# Dimmer_1_3.net
KiCad netlist of a schematic drawn in EAGLE
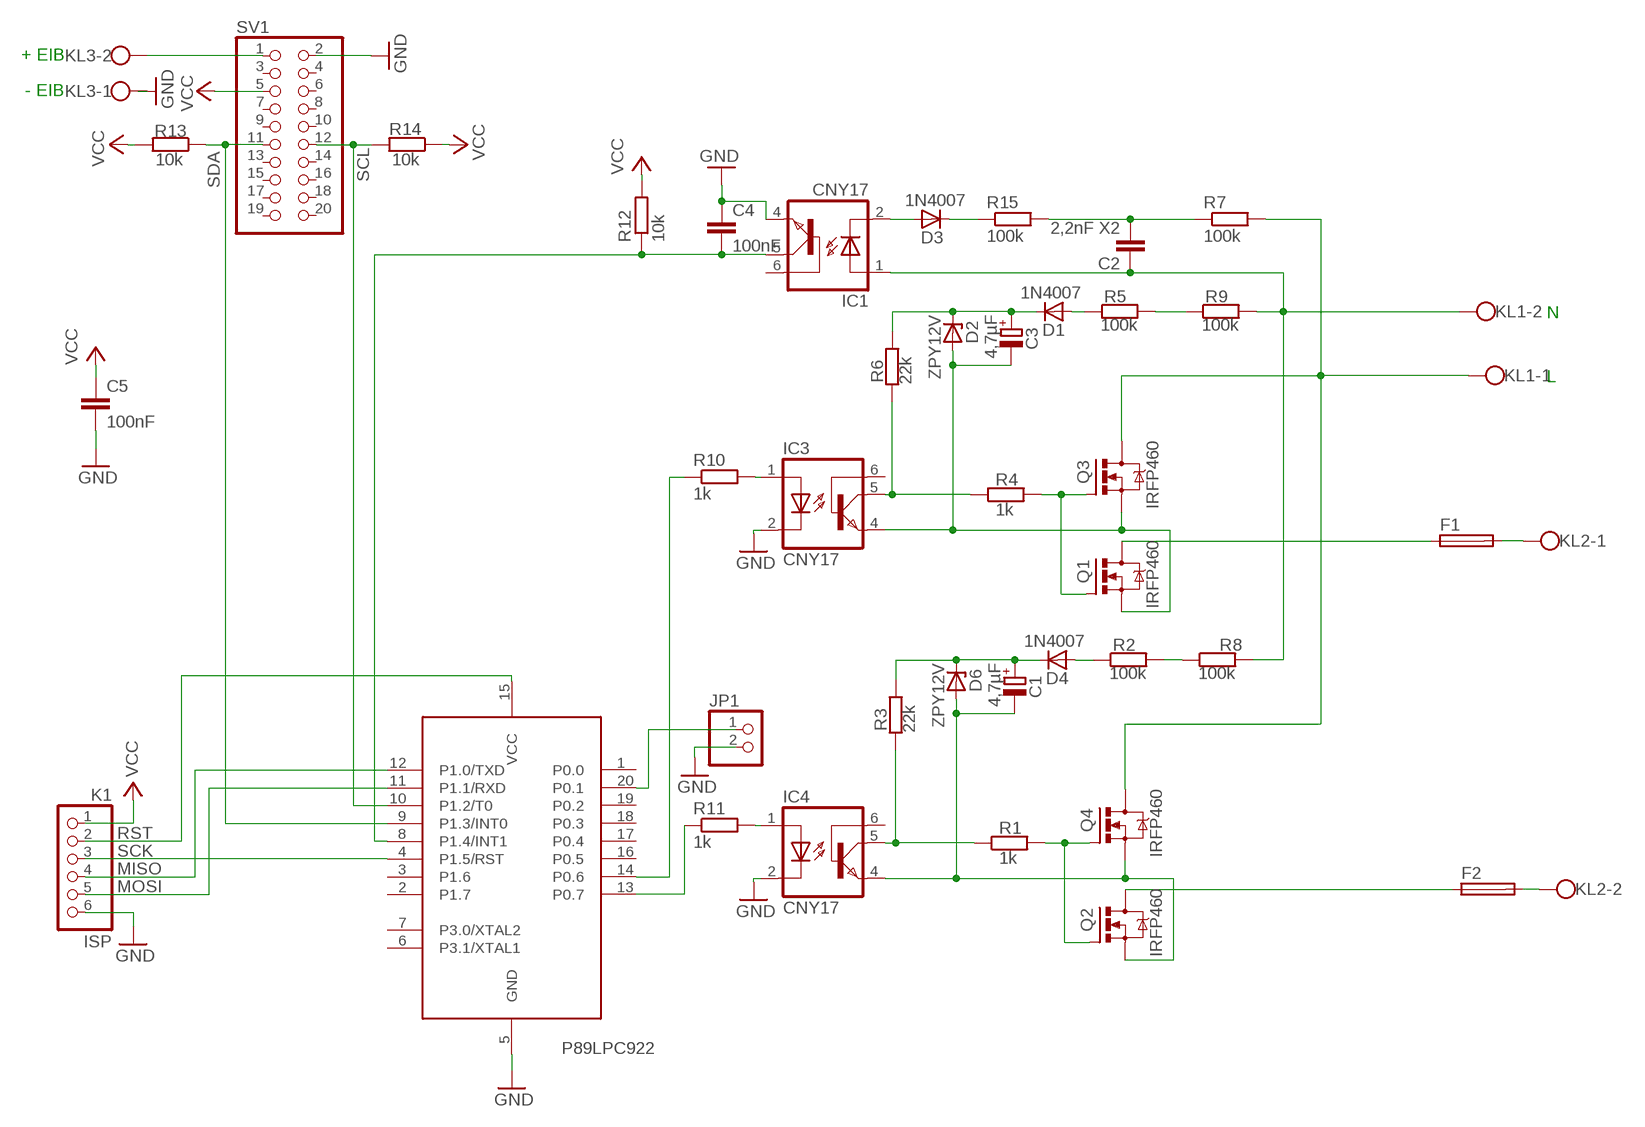
[diagram p0: schematic, sheet 1]

(export (version "E")
  (design (tool "Eeschema 10.0.6"))
  (components
    (comp (ref "C1")
      (value "4,7µF")
      (footprint "eagle-import:E2-4")
      (libsource (lib "eagle-import") (part "CPOL-EUE2-4"))
    )
    (comp (ref "C2")
      (value "2,2nF X2")
      (footprint "eagle-import:C075-063X106")
      (libsource (lib "eagle-import") (part "C-EU075-063X106"))
    )
    (comp (ref "C3")
      (value "4,7µF")
      (footprint "eagle-import:E2-4")
      (libsource (lib "eagle-import") (part "CPOL-EUE2-4"))
    )
    (comp (ref "C4")
      (value "100nF")
      (footprint "eagle-import:C050-024X044")
      (libsource (lib "eagle-import") (part "C-EU050-024X044"))
    )
    (comp (ref "C5")
      (value "100nF")
      (footprint "eagle-import:C025-024X044")
      (libsource (lib "eagle-import") (part "C-EU025-024X044"))
    )
    (comp (ref "D1")
      (value "1N4007")
      (footprint "eagle-import:DO35-10")
      (libsource (lib "eagle-import") (part "1N4148"))
    )
    (comp (ref "D2")
      (value "ZPY12V")
      (footprint "eagle-import:DO41Z10")
      (libsource (lib "eagle-import") (part "ZPY"))
    )
    (comp (ref "D3")
      (value "1N4007")
      (footprint "eagle-import:DO35-10")
      (libsource (lib "eagle-import") (part "1N4148"))
    )
    (comp (ref "D4")
      (value "1N4007")
      (footprint "eagle-import:DO35-10")
      (libsource (lib "eagle-import") (part "1N4148"))
    )
    (comp (ref "D6")
      (value "ZPY12V")
      (footprint "eagle-import:DO41Z10")
      (libsource (lib "eagle-import") (part "ZPY"))
    )
    (comp (ref "F1")
      (value "SH22,5")
      (footprint "eagle-import:SH22,5")
      (libsource (lib "eagle-import") (part "SH22,5"))
    )
    (comp (ref "F2")
      (value "SH22,5")
      (footprint "eagle-import:SH22,5")
      (libsource (lib "eagle-import") (part "SH22,5"))
    )
    (comp (ref "IC1")
      (value "CNY17")
      (footprint "eagle-import:DIL06")
      (libsource (lib "eagle-import") (part "CNY17"))
    )
    (comp (ref "IC2")
      (value "89LPC922")
      (footprint "eagle-import:DIL20")
      (libsource (lib "eagle-import") (part "89LPC922"))
    )
    (comp (ref "IC3")
      (value "CNY17")
      (footprint "eagle-import:DIL06")
      (libsource (lib "eagle-import") (part "CNY17"))
    )
    (comp (ref "IC4")
      (value "CNY17")
      (footprint "eagle-import:DIL06")
      (libsource (lib "eagle-import") (part "CNY17"))
    )
    (comp (ref "JP1")
      (value "PINHD-1X2")
      (footprint "eagle-import:1X02")
      (libsource (lib "eagle-import") (part "PINHD-1X2"))
    )
    (comp (ref "K1")
      (value "ISP")
      (footprint "eagle-import:1X06")
      (libsource (lib "eagle-import") (part "PINHD-1X6"))
    )
    (comp (ref "KL1")
      (value "W237-102")
      (footprint "eagle-import:W237-102")
      (libsource (lib "eagle-import") (part "W237-102"))
    )
    (comp (ref "KL2")
      (value "W237-102")
      (footprint "eagle-import:W237-102")
      (libsource (lib "eagle-import") (part "W237-102"))
    )
    (comp (ref "KL3")
      (value "W237-102")
      (footprint "eagle-import:W237-102")
      (libsource (lib "eagle-import") (part "W237-102"))
    )
    (comp (ref "Q1")
      (value "IRFP460")
      (footprint "eagle-import:TO247BV")
      (libsource (lib "eagle-import") (part "IRFPC40"))
    )
    (comp (ref "Q2")
      (value "IRFP460")
      (footprint "eagle-import:TO247BV")
      (libsource (lib "eagle-import") (part "IRFPC40"))
    )
    (comp (ref "Q3")
      (value "IRFP460")
      (footprint "eagle-import:TO247BV")
      (libsource (lib "eagle-import") (part "IRFPC40"))
    )
    (comp (ref "Q4")
      (value "IRFP460")
      (footprint "eagle-import:TO247BV")
      (libsource (lib "eagle-import") (part "IRFPC40"))
    )
    (comp (ref "R1")
      (value "1k")
      (footprint "eagle-import:0204_7")
      (libsource (lib "eagle-import") (part "R-EU_0204/7"))
    )
    (comp (ref "R2")
      (value "100k")
      (footprint "eagle-import:0204_7")
      (libsource (lib "eagle-import") (part "R-EU_0204/7"))
    )
    (comp (ref "R3")
      (value "22k")
      (footprint "eagle-import:0204_7")
      (libsource (lib "eagle-import") (part "R-EU_0204/7"))
    )
    (comp (ref "R4")
      (value "1k")
      (footprint "eagle-import:0204_7")
      (libsource (lib "eagle-import") (part "R-EU_0204/7"))
    )
    (comp (ref "R5")
      (value "100k")
      (footprint "eagle-import:0204_7")
      (libsource (lib "eagle-import") (part "R-EU_0204/7"))
    )
    (comp (ref "R6")
      (value "22k")
      (footprint "eagle-import:0204_7")
      (libsource (lib "eagle-import") (part "R-EU_0204/7"))
    )
    (comp (ref "R7")
      (value "100k")
      (footprint "eagle-import:0204_7")
      (libsource (lib "eagle-import") (part "R-EU_0204/7"))
    )
    (comp (ref "R8")
      (value "100k")
      (footprint "eagle-import:0204_7")
      (libsource (lib "eagle-import") (part "R-EU_0204/7"))
    )
    (comp (ref "R9")
      (value "100k")
      (footprint "eagle-import:0204_7")
      (libsource (lib "eagle-import") (part "R-EU_0204/7"))
    )
    (comp (ref "R10")
      (value "1k")
      (footprint "eagle-import:0204_7")
      (libsource (lib "eagle-import") (part "R-EU_0204/7"))
    )
    (comp (ref "R11")
      (value "1k")
      (footprint "eagle-import:0204_7")
      (libsource (lib "eagle-import") (part "R-EU_0204/7"))
    )
    (comp (ref "R12")
      (value "10k")
      (footprint "eagle-import:0204_7")
      (libsource (lib "eagle-import") (part "R-EU_0204/7"))
    )
    (comp (ref "R13")
      (value "10k")
      (footprint "eagle-import:0204_7")
      (libsource (lib "eagle-import") (part "R-EU_0204/7"))
    )
    (comp (ref "R14")
      (value "10k")
      (footprint "eagle-import:0204_7")
      (libsource (lib "eagle-import") (part "R-EU_0204/7"))
    )
    (comp (ref "R15")
      (value "100k")
      (footprint "eagle-import:0204_7")
      (libsource (lib "eagle-import") (part "R-EU_0204/7"))
    )
    (comp (ref "SV1")
      (value "PINHD-2X10")
      (footprint "eagle-import:2X10")
      (libsource (lib "eagle-import") (part "PINHD-2X10"))
    )
  )
  (nets
    (net (code "1") (name "/MISO") (class "Default")
      (node (ref "IC2") (pin "12") (pinfunction "P1.0/TXD_12") (pintype "bidirectional"))
      (node (ref "K1") (pin "4") (pinfunction "4_4") (pintype "passive"))
    )
    (net (code "2") (name "/MOSI") (class "Default")
      (node (ref "IC2") (pin "11") (pinfunction "P1.1/RXD_11") (pintype "bidirectional"))
      (node (ref "K1") (pin "5") (pinfunction "5_5") (pintype "passive"))
    )
    (net (code "3") (name "/RST") (class "Default")
      (node (ref "IC2") (pin "15") (pinfunction "VCC_15") (pintype "bidirectional"))
      (node (ref "K1") (pin "2") (pinfunction "2_2") (pintype "passive"))
    )
    (net (code "4") (name "/SCK") (class "Default")
      (node (ref "IC2") (pin "4") (pinfunction "P1.5/RST_4") (pintype "bidirectional"))
      (node (ref "K1") (pin "3") (pinfunction "3_3") (pintype "passive"))
    )
    (net (code "5") (name "/SCL") (class "Default")
      (node (ref "IC2") (pin "10") (pinfunction "P1.2/T0_10") (pintype "bidirectional"))
      (node (ref "R14") (pin "2") (pinfunction "2_2") (pintype "passive"))
      (node (ref "SV1") (pin "12") (pinfunction "12_12") (pintype "passive"))
    )
    (net (code "6") (name "/SDA") (class "Default")
      (node (ref "IC2") (pin "9") (pinfunction "P1.3/INT0_9") (pintype "bidirectional"))
      (node (ref "R13") (pin "1") (pinfunction "1_1") (pintype "passive"))
      (node (ref "SV1") (pin "11") (pinfunction "11_11") (pintype "passive"))
    )
    (net (code "7") (name "GND") (class "Default")
      (node (ref "C4") (pin "1") (pinfunction "1_1") (pintype "passive"))
      (node (ref "C5") (pin "2") (pinfunction "2_2") (pintype "passive"))
      (node (ref "IC1") (pin "4") (pinfunction "EMI_4") (pintype "passive"))
      (node (ref "IC2") (pin "5") (pinfunction "GND_5") (pintype "bidirectional"))
      (node (ref "IC3") (pin "2") (pinfunction "C_2") (pintype "passive"))
      (node (ref "IC4") (pin "2") (pinfunction "C_2") (pintype "passive"))
      (node (ref "JP1") (pin "2") (pinfunction "2_2") (pintype "passive"))
      (node (ref "K1") (pin "6") (pinfunction "6_6") (pintype "passive"))
      (node (ref "KL3") (pin "1") (pinfunction "KL_1") (pintype "passive"))
      (node (ref "SV1") (pin "2") (pinfunction "2_2") (pintype "passive"))
    )
    (net (code "8") (name "Net-(C1-Pad+)") (class "Default")
      (node (ref "C1") (pin "+") (pinfunction "+_+") (pintype "passive"))
      (node (ref "D4") (pin "C") (pinfunction "C_C") (pintype "passive"))
      (node (ref "D6") (pin "C") (pinfunction "C_C") (pintype "passive"))
      (node (ref "R3") (pin "2") (pinfunction "2_2") (pintype "passive"))
    )
    (net (code "9") (name "Net-(C2-Pad2)") (class "Default")
      (node (ref "C2") (pin "2") (pinfunction "2_2") (pintype "passive"))
      (node (ref "R15") (pin "2") (pinfunction "2_2") (pintype "passive"))
      (node (ref "R7") (pin "1") (pinfunction "1_1") (pintype "passive"))
    )
    (net (code "10") (name "Net-(C3-Pad+)") (class "Default")
      (node (ref "C3") (pin "+") (pinfunction "+_+") (pintype "passive"))
      (node (ref "D1") (pin "C") (pinfunction "C_C") (pintype "passive"))
      (node (ref "D2") (pin "C") (pinfunction "C_C") (pintype "passive"))
      (node (ref "R6") (pin "2") (pinfunction "2_2") (pintype "passive"))
    )
    (net (code "11") (name "Net-(D1-PadA)") (class "Default")
      (node (ref "D1") (pin "A") (pinfunction "A_A") (pintype "passive"))
      (node (ref "R5") (pin "1") (pinfunction "1_1") (pintype "passive"))
    )
    (net (code "12") (name "Net-(D3-PadC)") (class "Default")
      (node (ref "D3") (pin "C") (pinfunction "C_C") (pintype "passive"))
      (node (ref "R15") (pin "1") (pinfunction "1_1") (pintype "passive"))
    )
    (net (code "13") (name "Net-(D4-PadA)") (class "Default")
      (node (ref "D4") (pin "A") (pinfunction "A_A") (pintype "passive"))
      (node (ref "R2") (pin "1") (pinfunction "1_1") (pintype "passive"))
    )
    (net (code "14") (name "Net-(F1-Pad1)") (class "Default")
      (node (ref "F1") (pin "1") (pinfunction "1_1") (pintype "passive"))
      (node (ref "Q1") (pin "D") (pinfunction "D_D") (pintype "passive"))
    )
    (net (code "15") (name "Net-(F2-Pad1)") (class "Default")
      (node (ref "F2") (pin "1") (pinfunction "1_1") (pintype "passive"))
      (node (ref "Q2") (pin "D") (pinfunction "D_D") (pintype "passive"))
    )
    (net (code "16") (name "Net-(IC1-A)") (class "Default")
      (node (ref "C2") (pin "1") (pinfunction "1_1") (pintype "passive"))
      (node (ref "IC1") (pin "1") (pinfunction "A_1") (pintype "passive"))
      (node (ref "KL1") (pin "2") (pinfunction "KL_2") (pintype "passive"))
      (node (ref "R8") (pin "2") (pinfunction "2_2") (pintype "passive"))
      (node (ref "R9") (pin "2") (pinfunction "2_2") (pintype "passive"))
    )
    (net (code "17") (name "Net-(IC1-C)") (class "Default")
      (node (ref "D3") (pin "A") (pinfunction "A_A") (pintype "passive"))
      (node (ref "IC1") (pin "2") (pinfunction "C_2") (pintype "passive"))
    )
    (net (code "18") (name "Net-(IC1-COL)") (class "Default")
      (node (ref "C4") (pin "2") (pinfunction "2_2") (pintype "passive"))
      (node (ref "IC1") (pin "5") (pinfunction "COL_5") (pintype "passive"))
      (node (ref "IC2") (pin "8") (pinfunction "P1.4/INT1_8") (pintype "bidirectional"))
      (node (ref "R12") (pin "1") (pinfunction "1_1") (pintype "passive"))
    )
    (net (code "19") (name "Net-(IC2-P0.1)") (class "Default")
      (node (ref "IC2") (pin "20") (pinfunction "P0.1_20") (pintype "bidirectional"))
      (node (ref "JP1") (pin "1") (pinfunction "1_1") (pintype "passive"))
    )
    (net (code "20") (name "Net-(IC2-P0.6)") (class "Default")
      (node (ref "IC2") (pin "14") (pinfunction "P0.6_14") (pintype "bidirectional"))
      (node (ref "R10") (pin "1") (pinfunction "1_1") (pintype "passive"))
    )
    (net (code "21") (name "Net-(IC2-P0.7)") (class "Default")
      (node (ref "IC2") (pin "13") (pinfunction "P0.7_13") (pintype "bidirectional"))
      (node (ref "R11") (pin "1") (pinfunction "1_1") (pintype "passive"))
    )
    (net (code "22") (name "Net-(IC3-A)") (class "Default")
      (node (ref "IC3") (pin "1") (pinfunction "A_1") (pintype "passive"))
      (node (ref "R10") (pin "2") (pinfunction "2_2") (pintype "passive"))
    )
    (net (code "23") (name "Net-(IC3-COL)") (class "Default")
      (node (ref "IC3") (pin "5") (pinfunction "COL_5") (pintype "passive"))
      (node (ref "R4") (pin "1") (pinfunction "1_1") (pintype "passive"))
      (node (ref "R6") (pin "1") (pinfunction "1_1") (pintype "passive"))
    )
    (net (code "24") (name "Net-(IC3-EMI)") (class "Default")
      (node (ref "C3") (pin "-") (pinfunction "-_-") (pintype "passive"))
      (node (ref "D2") (pin "A") (pinfunction "A_A") (pintype "passive"))
      (node (ref "IC3") (pin "4") (pinfunction "EMI_4") (pintype "passive"))
      (node (ref "Q1") (pin "S") (pinfunction "S_S") (pintype "passive"))
      (node (ref "Q3") (pin "S") (pinfunction "S_S") (pintype "passive"))
    )
    (net (code "25") (name "Net-(IC4-A)") (class "Default")
      (node (ref "IC4") (pin "1") (pinfunction "A_1") (pintype "passive"))
      (node (ref "R11") (pin "2") (pinfunction "2_2") (pintype "passive"))
    )
    (net (code "26") (name "Net-(IC4-COL)") (class "Default")
      (node (ref "IC4") (pin "5") (pinfunction "COL_5") (pintype "passive"))
      (node (ref "R1") (pin "1") (pinfunction "1_1") (pintype "passive"))
      (node (ref "R3") (pin "1") (pinfunction "1_1") (pintype "passive"))
    )
    (net (code "27") (name "Net-(IC4-EMI)") (class "Default")
      (node (ref "C1") (pin "-") (pinfunction "-_-") (pintype "passive"))
      (node (ref "D6") (pin "A") (pinfunction "A_A") (pintype "passive"))
      (node (ref "IC4") (pin "4") (pinfunction "EMI_4") (pintype "passive"))
      (node (ref "Q2") (pin "S") (pinfunction "S_S") (pintype "passive"))
      (node (ref "Q4") (pin "S") (pinfunction "S_S") (pintype "passive"))
    )
    (net (code "28") (name "Net-(KL1A-KL)") (class "Default")
      (node (ref "KL1") (pin "1") (pinfunction "KL_1") (pintype "passive"))
      (node (ref "Q3") (pin "D") (pinfunction "D_D") (pintype "passive"))
      (node (ref "Q4") (pin "D") (pinfunction "D_D") (pintype "passive"))
      (node (ref "R7") (pin "2") (pinfunction "2_2") (pintype "passive"))
    )
    (net (code "29") (name "Net-(KL2A-KL)") (class "Default")
      (node (ref "F1") (pin "2") (pinfunction "2_2") (pintype "passive"))
      (node (ref "KL2") (pin "1") (pinfunction "KL_1") (pintype "passive"))
    )
    (net (code "30") (name "Net-(KL2B-KL)") (class "Default")
      (node (ref "F2") (pin "2") (pinfunction "2_2") (pintype "passive"))
      (node (ref "KL2") (pin "2") (pinfunction "KL_2") (pintype "passive"))
    )
    (net (code "31") (name "Net-(KL3B-KL)") (class "Default")
      (node (ref "KL3") (pin "2") (pinfunction "KL_2") (pintype "passive"))
      (node (ref "SV1") (pin "1") (pinfunction "1_1") (pintype "passive"))
    )
    (net (code "32") (name "Net-(Q1-PadG)") (class "Default")
      (node (ref "Q1") (pin "G") (pinfunction "G_G") (pintype "passive"))
      (node (ref "Q3") (pin "G") (pinfunction "G_G") (pintype "passive"))
      (node (ref "R4") (pin "2") (pinfunction "2_2") (pintype "passive"))
    )
    (net (code "33") (name "Net-(Q2-PadG)") (class "Default")
      (node (ref "Q2") (pin "G") (pinfunction "G_G") (pintype "passive"))
      (node (ref "Q4") (pin "G") (pinfunction "G_G") (pintype "passive"))
      (node (ref "R1") (pin "2") (pinfunction "2_2") (pintype "passive"))
    )
    (net (code "34") (name "Net-(R2-Pad2)") (class "Default")
      (node (ref "R2") (pin "2") (pinfunction "2_2") (pintype "passive"))
      (node (ref "R8") (pin "1") (pinfunction "1_1") (pintype "passive"))
    )
    (net (code "35") (name "Net-(R5-Pad2)") (class "Default")
      (node (ref "R5") (pin "2") (pinfunction "2_2") (pintype "passive"))
      (node (ref "R9") (pin "1") (pinfunction "1_1") (pintype "passive"))
    )
    (net (code "36") (name "VCC") (class "Default")
      (node (ref "C5") (pin "1") (pinfunction "1_1") (pintype "passive"))
      (node (ref "K1") (pin "1") (pinfunction "1_1") (pintype "passive"))
      (node (ref "R12") (pin "2") (pinfunction "2_2") (pintype "passive"))
      (node (ref "R13") (pin "2") (pinfunction "2_2") (pintype "passive"))
      (node (ref "R14") (pin "1") (pinfunction "1_1") (pintype "passive"))
      (node (ref "SV1") (pin "5") (pinfunction "5_5") (pintype "passive"))
    )
    (net (code "37") (name "unconnected-(IC1-BAS-Pad6)") (class "Default")
      (node (ref "IC1") (pin "6") (pinfunction "BAS_6") (pintype "passive"))
    )
    (net (code "38") (name "unconnected-(IC2-P0.0-Pad1)") (class "Default")
      (node (ref "IC2") (pin "1") (pinfunction "P0.0_1") (pintype "bidirectional"))
    )
    (net (code "39") (name "unconnected-(IC2-P0.2-Pad19)") (class "Default")
      (node (ref "IC2") (pin "19") (pinfunction "P0.2_19") (pintype "bidirectional"))
    )
    (net (code "40") (name "unconnected-(IC2-P0.3-Pad18)") (class "Default")
      (node (ref "IC2") (pin "18") (pinfunction "P0.3_18") (pintype "bidirectional"))
    )
    (net (code "41") (name "unconnected-(IC2-P0.4-Pad17)") (class "Default")
      (node (ref "IC2") (pin "17") (pinfunction "P0.4_17") (pintype "bidirectional"))
    )
    (net (code "42") (name "unconnected-(IC2-P0.5-Pad16)") (class "Default")
      (node (ref "IC2") (pin "16") (pinfunction "P0.5_16") (pintype "bidirectional"))
    )
    (net (code "43") (name "unconnected-(IC2-P1.6-Pad3)") (class "Default")
      (node (ref "IC2") (pin "3") (pinfunction "P1.6_3") (pintype "bidirectional"))
    )
    (net (code "44") (name "unconnected-(IC2-P1.7-Pad2)") (class "Default")
      (node (ref "IC2") (pin "2") (pinfunction "P1.7_2") (pintype "bidirectional"))
    )
    (net (code "45") (name "unconnected-(IC2-P3.0{slash}XTAL2-Pad7)") (class "Default")
      (node (ref "IC2") (pin "7") (pinfunction "P3.0/XTAL2_7") (pintype "bidirectional"))
    )
    (net (code "46") (name "unconnected-(IC2-P3.1{slash}XTAL1-Pad6)") (class "Default")
      (node (ref "IC2") (pin "6") (pinfunction "P3.1/XTAL1_6") (pintype "bidirectional"))
    )
    (net (code "47") (name "unconnected-(IC3-BAS-Pad6)") (class "Default")
      (node (ref "IC3") (pin "6") (pinfunction "BAS_6") (pintype "passive"))
    )
    (net (code "48") (name "unconnected-(IC4-BAS-Pad6)") (class "Default")
      (node (ref "IC4") (pin "6") (pinfunction "BAS_6") (pintype "passive"))
    )
    (net (code "49") (name "unconnected-(SV1-Pad3)") (class "Default")
      (node (ref "SV1") (pin "3") (pinfunction "3_3") (pintype "passive"))
    )
    (net (code "50") (name "unconnected-(SV1-Pad4)") (class "Default")
      (node (ref "SV1") (pin "4") (pinfunction "4_4") (pintype "passive"))
    )
    (net (code "51") (name "unconnected-(SV1-Pad6)") (class "Default")
      (node (ref "SV1") (pin "6") (pinfunction "6_6") (pintype "passive"))
    )
    (net (code "52") (name "unconnected-(SV1-Pad7)") (class "Default")
      (node (ref "SV1") (pin "7") (pinfunction "7_7") (pintype "passive"))
    )
    (net (code "53") (name "unconnected-(SV1-Pad8)") (class "Default")
      (node (ref "SV1") (pin "8") (pinfunction "8_8") (pintype "passive"))
    )
    (net (code "54") (name "unconnected-(SV1-Pad9)") (class "Default")
      (node (ref "SV1") (pin "9") (pinfunction "9_9") (pintype "passive"))
    )
    (net (code "55") (name "unconnected-(SV1-Pad10)") (class "Default")
      (node (ref "SV1") (pin "10") (pinfunction "10_10") (pintype "passive"))
    )
    (net (code "56") (name "unconnected-(SV1-Pad13)") (class "Default")
      (node (ref "SV1") (pin "13") (pinfunction "13_13") (pintype "passive"))
    )
    (net (code "57") (name "unconnected-(SV1-Pad14)") (class "Default")
      (node (ref "SV1") (pin "14") (pinfunction "14_14") (pintype "passive"))
    )
    (net (code "58") (name "unconnected-(SV1-Pad15)") (class "Default")
      (node (ref "SV1") (pin "15") (pinfunction "15_15") (pintype "passive"))
    )
    (net (code "59") (name "unconnected-(SV1-Pad16)") (class "Default")
      (node (ref "SV1") (pin "16") (pinfunction "16_16") (pintype "passive"))
    )
    (net (code "60") (name "unconnected-(SV1-Pad17)") (class "Default")
      (node (ref "SV1") (pin "17") (pinfunction "17_17") (pintype "passive"))
    )
    (net (code "61") (name "unconnected-(SV1-Pad18)") (class "Default")
      (node (ref "SV1") (pin "18") (pinfunction "18_18") (pintype "passive"))
    )
    (net (code "62") (name "unconnected-(SV1-Pad19)") (class "Default")
      (node (ref "SV1") (pin "19") (pinfunction "19_19") (pintype "passive"))
    )
    (net (code "63") (name "unconnected-(SV1-Pad20)") (class "Default")
      (node (ref "SV1") (pin "20") (pinfunction "20_20") (pintype "passive"))
    )
  )
)
